# 3_wave_VCO.net
KiCad netlist of a schematic drawn in Altium Designer
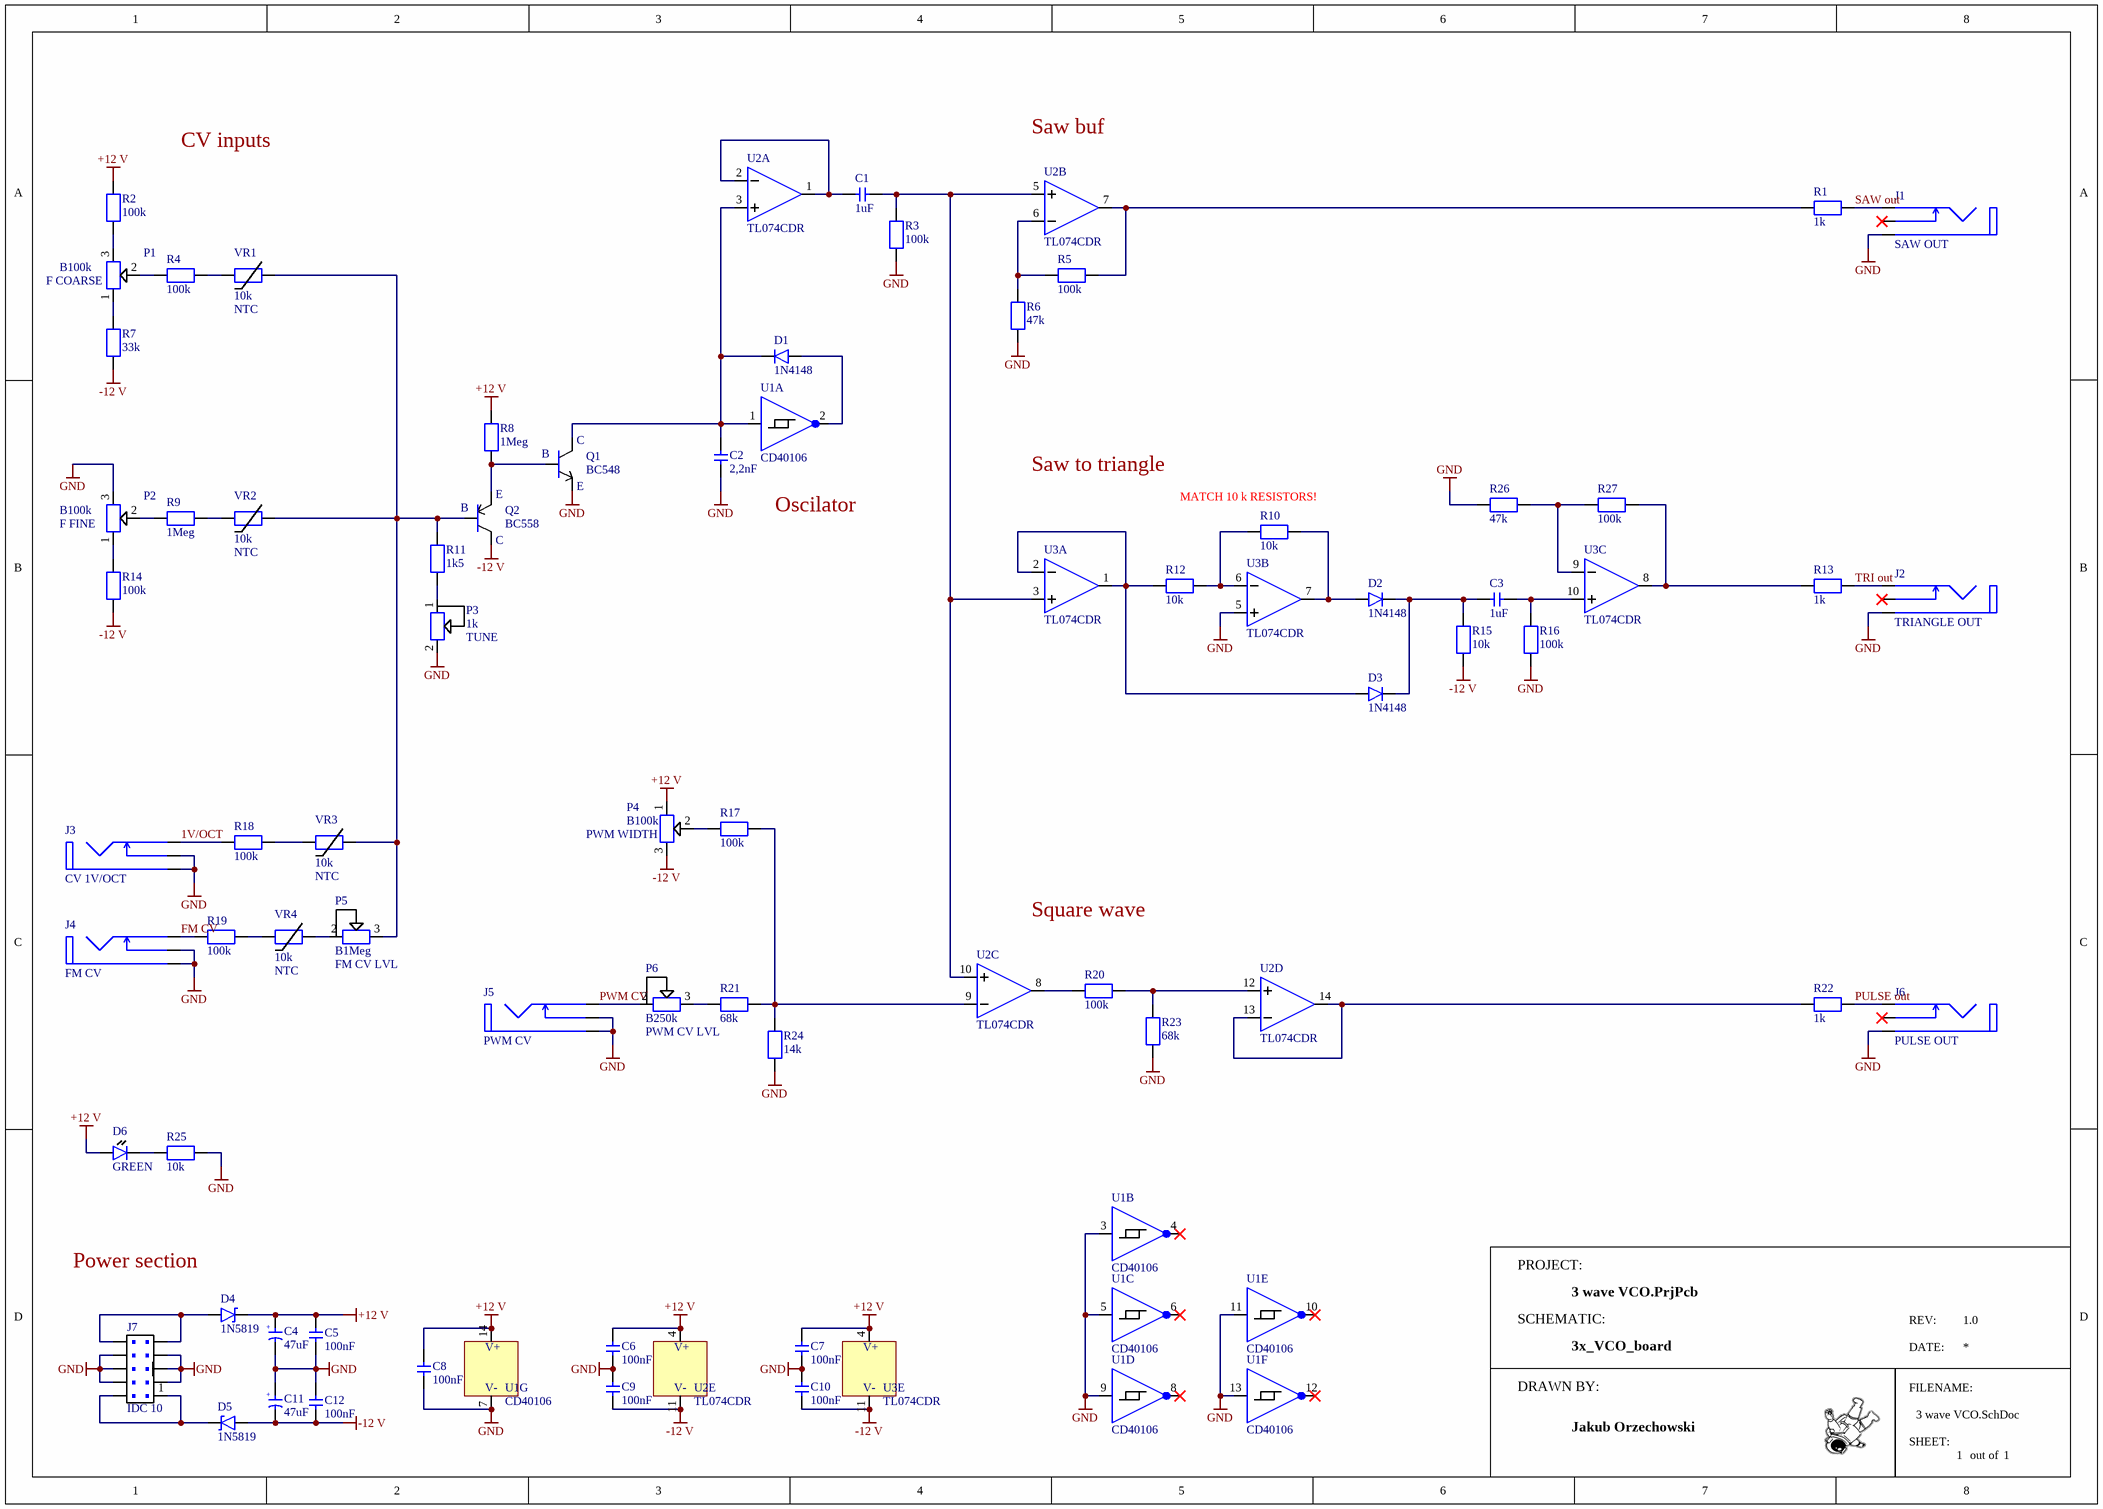
[diagram p0: 3 wave VCO.SchDoc]

(export (version "E")
  (design (tool "Eeschema 10.0.6"))
  (components
    (comp (ref "C1")
      (value "1uF")
      (footprint "Cap THT 5mm")
      (description "THT Capacitor Non-Polarised 5 mm Pitch")
      (fields (field (name "Comment") "CAP"))
      (libsource (lib "Generic components") (part "Capacitor THT 5mm"))
    )
    (comp (ref "C2")
      (value "2,2nF")
      (footprint "Cap THT 5mm")
      (description "THT Capacitor Non-Polarised 5 mm Pitch")
      (fields (field (name "Comment") "CAP"))
      (libsource (lib "Generic components") (part "Capacitor THT 5mm"))
    )
    (comp (ref "C3")
      (value "1uF")
      (footprint "Cap THT 5mm")
      (description "THT Capacitor Non-Polarised 5 mm Pitch")
      (fields (field (name "Comment") "CAP"))
      (libsource (lib "Generic components") (part "Capacitor THT 5mm"))
    )
    (comp (ref "C4")
      (value "47uF")
      (footprint "Cap electrolytic THT 5mm")
      (description "THT Electrolytic Capacitor 5 mm Diameter")
      (fields (field (name "Comment") "CAP"))
      (libsource (lib "Generic components") (part "Capacitor Electr THT 5mm"))
    )
    (comp (ref "C5")
      (value "100nF")
      (footprint "Cap THT 5mm")
      (description "THT Capacitor Non-Polarised 5 mm Pitch")
      (fields (field (name "Comment") "CAP"))
      (libsource (lib "Generic components") (part "Capacitor THT 5mm"))
    )
    (comp (ref "C6")
      (value "100nF")
      (footprint "Cap THT 5mm")
      (description "THT Capacitor Non-Polarised 5 mm Pitch")
      (fields (field (name "Comment") "CAP"))
      (libsource (lib "Generic components") (part "Capacitor THT 5mm"))
    )
    (comp (ref "C7")
      (value "100nF")
      (footprint "Cap THT 5mm")
      (description "THT Capacitor Non-Polarised 5 mm Pitch")
      (fields (field (name "Comment") "CAP"))
      (libsource (lib "Generic components") (part "Capacitor THT 5mm"))
    )
    (comp (ref "C8")
      (value "100nF")
      (footprint "Cap THT 5mm")
      (description "THT Capacitor Non-Polarised 5 mm Pitch")
      (fields (field (name "Comment") "CAP"))
      (libsource (lib "Generic components") (part "Capacitor THT 5mm"))
    )
    (comp (ref "C9")
      (value "100nF")
      (footprint "Cap THT 5mm")
      (description "THT Capacitor Non-Polarised 5 mm Pitch")
      (fields (field (name "Comment") "CAP"))
      (libsource (lib "Generic components") (part "Capacitor THT 5mm"))
    )
    (comp (ref "C10")
      (value "100nF")
      (footprint "Cap THT 5mm")
      (description "THT Capacitor Non-Polarised 5 mm Pitch")
      (fields (field (name "Comment") "CAP"))
      (libsource (lib "Generic components") (part "Capacitor THT 5mm"))
    )
    (comp (ref "C11")
      (value "47uF")
      (footprint "Cap electrolytic THT 5mm")
      (description "THT Electrolytic Capacitor 5 mm Diameter")
      (fields (field (name "Comment") "CAP"))
      (libsource (lib "Generic components") (part "Capacitor Electr THT 5mm"))
    )
    (comp (ref "C12")
      (value "100nF")
      (footprint "Cap THT 5mm")
      (description "THT Capacitor Non-Polarised 5 mm Pitch")
      (fields (field (name "Comment") "CAP"))
      (libsource (lib "Generic components") (part "Capacitor THT 5mm"))
    )
    (comp (ref "D1")
      (value "DIODE")
      (footprint "Diode THT 10 mm")
      (description "Generic THT Axial Diode 10 mm Pitch")
      (fields (field (name "MODEL") "1N4148"))
      (libsource (lib "Diodes") (part "Diode THT"))
    )
    (comp (ref "D2")
      (value "DIODE")
      (footprint "Diode THT 10 mm")
      (description "Generic THT Axial Diode 10 mm Pitch")
      (fields (field (name "MODEL") "1N4148"))
      (libsource (lib "Diodes") (part "Diode THT"))
    )
    (comp (ref "D3")
      (value "DIODE")
      (footprint "Diode THT 10 mm")
      (description "Generic THT Axial Diode 10 mm Pitch")
      (fields (field (name "MODEL") "1N4148"))
      (libsource (lib "Diodes") (part "Diode THT"))
    )
    (comp (ref "D4")
      (value "SCHOTTKY")
      (footprint "Diode THT 10 mm")
      (description "Generic THT Axial Schottky Diode 10 mm Pitch")
      (fields (field (name "MODEL") "1N5819"))
      (libsource (lib "Diodes") (part "Schottky Diode THT"))
    )
    (comp (ref "D5")
      (value "SCHOTTKY")
      (footprint "Diode THT 10 mm")
      (description "Generic THT Axial Schottky Diode 10 mm Pitch")
      (fields (field (name "MODEL") "1N5819"))
      (libsource (lib "Diodes") (part "Schottky Diode THT"))
    )
    (comp (ref "D6")
      (value "LED")
      (footprint "LED SMD 0805")
      (description "SMD LED Diode 0805 Package")
      (fields (field (name "COLOR") "GREEN"))
      (libsource (lib "Opto") (part "LED SMD"))
    )
    (comp (ref "J1")
      (value "JACK Mono")
      (footprint "PJ301M")
      (description "PJ301M Eurorack 3,5 mm Patch Socket PCB Mount")
      (fields (field (name "LABEL") "SAW OUT"))
      (libsource (lib "Connectors") (part "PJ301M"))
    )
    (comp (ref "J2")
      (value "JACK Mono")
      (footprint "PJ301M")
      (description "PJ301M Eurorack 3,5 mm Patch Socket PCB Mount")
      (fields (field (name "LABEL") "TRIANGLE OUT"))
      (libsource (lib "Connectors") (part "PJ301M"))
    )
    (comp (ref "J3")
      (value "JACK Mono")
      (footprint "PJ301M")
      (description "PJ301M Eurorack 3,5 mm Patch Socket PCB Mount")
      (fields (field (name "LABEL") "CV 1V/OCT"))
      (libsource (lib "Connectors") (part "PJ301M"))
    )
    (comp (ref "J4")
      (value "JACK Mono")
      (footprint "PJ301M")
      (description "PJ301M Eurorack 3,5 mm Patch Socket PCB Mount")
      (fields (field (name "LABEL") "FM CV"))
      (libsource (lib "Connectors") (part "PJ301M"))
    )
    (comp (ref "J5")
      (value "JACK Mono")
      (footprint "PJ301M")
      (description "PJ301M Eurorack 3,5 mm Patch Socket PCB Mount")
      (fields (field (name "LABEL") "PWM CV"))
      (libsource (lib "Connectors") (part "PJ301M"))
    )
    (comp (ref "J6")
      (value "JACK Mono")
      (footprint "PJ301M")
      (description "PJ301M Eurorack 3,5 mm Patch Socket PCB Mount")
      (fields (field (name "LABEL") "PULSE OUT"))
      (libsource (lib "Connectors") (part "PJ301M"))
    )
    (comp (ref "J7")
      (value "IDC 10")
      (footprint "IDC 10 PIN")
      (description "10 Pin IDC Connector")
      (libsource (lib "Connectors") (part "IDC 10 pin"))
    )
    (comp (ref "P1")
      (value "B100k")
      (footprint "Alpha 9mm mono")
      (description "PCB Mount Alpha 9mm Mono Potentiometer THT")
      (fields (field (name "PARAMETER") "F COARSE") (field (name "Comment") "Mono Pot"))
      (libsource (lib "Potentiometers") (part "Potentiometer Alpha 9mm mono"))
    )
    (comp (ref "P2")
      (value "B100k")
      (footprint "9 mm PCB Potentiometer")
      (description "PCB Mount 9mm Mono Potentiometer THT")
      (fields (field (name "PARAMETER") "F FINE") (field (name "Comment") "Mono Pot"))
      (libsource (lib "Potentiometers") (part "Potentiometer 9 mm"))
    )
    (comp (ref "P3")
      (value "1k")
      (footprint "Multiturn Potentiometer inline")
      (description "PCB Mount Multiturn Trimmer Potentiometer Top Adjustable as Variable Resistor Clockwise Increase")
      (fields (field (name "PARAMETER") "TUNE") (field (name "Comment") "VR"))
      (libsource (lib "Potentiometers") (part "VR A Multiturn THT"))
    )
    (comp (ref "P4")
      (value "B100k")
      (footprint "9 mm PCB Potentiometer")
      (description "PCB Mount 9mm Mono Potentiometer THT")
      (fields (field (name "PARAMETER") "PWM WIDTH") (field (name "Comment") "Mono Pot"))
      (libsource (lib "Potentiometers") (part "Potentiometer 9 mm"))
    )
    (comp (ref "P5")
      (value "B1Meg")
      (footprint "9 mm PCB Potentiometer")
      (description "PCB Mount 9mm Mono Potentiometer THT as Variable Resistor Clockwise Decrease")
      (fields (field (name "PARAMETER") "FM CV LVL") (field (name "Comment") "VR"))
      (libsource (lib "Potentiometers") (part "VR B 9 mm"))
    )
    (comp (ref "P6")
      (value "B250k")
      (footprint "9 mm PCB Potentiometer")
      (description "PCB Mount 9mm Mono Potentiometer THT as Variable Resistor Clockwise Decrease")
      (fields (field (name "PARAMETER") "PWM CV LVL") (field (name "Comment") "VR"))
      (libsource (lib "Potentiometers") (part "VR B 9 mm"))
    )
    (comp (ref "Q1")
      (value "BC548")
      (footprint "TO-92 wide")
      (description "BC548 NPN Transistor THT TO-92 Package")
      (libsource (lib "Transistors") (part "BC548"))
    )
    (comp (ref "Q2")
      (value "BC558")
      (footprint "TO-92 wide")
      (description "BC558 PNP Transistor THT TO-92 Package")
      (libsource (lib "Transistors") (part "BC558"))
    )
    (comp (ref "R1")
      (value "1k")
      (footprint "Resistor THT vertical")
      (description "THT Axial Resistor 10mm Pitch")
      (fields (field (name "Comment") "RES"))
      (libsource (lib "Generic components") (part "Resistor THT"))
    )
    (comp (ref "R2")
      (value "100k")
      (footprint "Resistor THT vertical")
      (description "THT Axial Resistor 10mm Pitch")
      (fields (field (name "Comment") "RES"))
      (libsource (lib "Generic components") (part "Resistor THT"))
    )
    (comp (ref "R3")
      (value "100k")
      (footprint "Resistor THT vertical")
      (description "THT Axial Resistor 10mm Pitch")
      (fields (field (name "Comment") "RES"))
      (libsource (lib "Generic components") (part "Resistor THT"))
    )
    (comp (ref "R4")
      (value "100k")
      (footprint "Resistor THT vertical")
      (description "THT Axial Resistor 10mm Pitch")
      (fields (field (name "Comment") "RES"))
      (libsource (lib "Generic components") (part "Resistor THT"))
    )
    (comp (ref "R5")
      (value "100k")
      (footprint "Resistor THT vertical")
      (description "THT Axial Resistor 10mm Pitch")
      (fields (field (name "Comment") "RES"))
      (libsource (lib "Generic components") (part "Resistor THT"))
    )
    (comp (ref "R6")
      (value "47k")
      (footprint "Resistor THT vertical")
      (description "THT Axial Resistor 10mm Pitch")
      (fields (field (name "Comment") "RES"))
      (libsource (lib "Generic components") (part "Resistor THT"))
    )
    (comp (ref "R7")
      (value "33k")
      (footprint "Resistor THT vertical")
      (description "THT Axial Resistor 10mm Pitch")
      (fields (field (name "Comment") "RES"))
      (libsource (lib "Generic components") (part "Resistor THT"))
    )
    (comp (ref "R8")
      (value "1Meg")
      (footprint "Resistor THT vertical")
      (description "THT Axial Resistor 10mm Pitch")
      (fields (field (name "Comment") "RES"))
      (libsource (lib "Generic components") (part "Resistor THT"))
    )
    (comp (ref "R9")
      (value "1Meg")
      (footprint "Resistor THT vertical")
      (description "THT Axial Resistor 10mm Pitch")
      (fields (field (name "Comment") "RES"))
      (libsource (lib "Generic components") (part "Resistor THT"))
    )
    (comp (ref "R10")
      (value "10k")
      (footprint "Resistor THT vertical")
      (description "THT Axial Resistor 10mm Pitch")
      (fields (field (name "Comment") "RES"))
      (libsource (lib "Generic components") (part "Resistor THT"))
    )
    (comp (ref "R11")
      (value "1k5")
      (footprint "Resistor THT vertical")
      (description "THT Axial Resistor 10mm Pitch")
      (fields (field (name "Comment") "RES"))
      (libsource (lib "Generic components") (part "Resistor THT"))
    )
    (comp (ref "R12")
      (value "10k")
      (footprint "Resistor THT vertical")
      (description "THT Axial Resistor 10mm Pitch")
      (fields (field (name "Comment") "RES"))
      (libsource (lib "Generic components") (part "Resistor THT"))
    )
    (comp (ref "R13")
      (value "1k")
      (footprint "Resistor THT vertical")
      (description "THT Axial Resistor 10mm Pitch")
      (fields (field (name "Comment") "RES"))
      (libsource (lib "Generic components") (part "Resistor THT"))
    )
    (comp (ref "R14")
      (value "100k")
      (footprint "Resistor THT vertical")
      (description "THT Axial Resistor 10mm Pitch")
      (fields (field (name "Comment") "RES"))
      (libsource (lib "Generic components") (part "Resistor THT"))
    )
    (comp (ref "R15")
      (value "10k")
      (footprint "Resistor THT vertical")
      (description "THT Axial Resistor 10mm Pitch")
      (fields (field (name "Comment") "RES"))
      (libsource (lib "Generic components") (part "Resistor THT"))
    )
    (comp (ref "R16")
      (value "100k")
      (footprint "Resistor THT vertical")
      (description "THT Axial Resistor 10mm Pitch")
      (fields (field (name "Comment") "RES"))
      (libsource (lib "Generic components") (part "Resistor THT"))
    )
    (comp (ref "R17")
      (value "100k")
      (footprint "Resistor THT vertical")
      (description "THT Axial Resistor 10mm Pitch")
      (fields (field (name "Comment") "RES"))
      (libsource (lib "Generic components") (part "Resistor THT"))
    )
    (comp (ref "R18")
      (value "100k")
      (footprint "Resistor THT vertical")
      (description "THT Axial Resistor 10mm Pitch")
      (fields (field (name "Comment") "RES"))
      (libsource (lib "Generic components") (part "Resistor THT"))
    )
    (comp (ref "R19")
      (value "100k")
      (footprint "Resistor THT vertical")
      (description "THT Axial Resistor 10mm Pitch")
      (fields (field (name "Comment") "RES"))
      (libsource (lib "Generic components") (part "Resistor THT"))
    )
    (comp (ref "R20")
      (value "100k")
      (footprint "Resistor THT vertical")
      (description "THT Axial Resistor 10mm Pitch")
      (fields (field (name "Comment") "RES"))
      (libsource (lib "Generic components") (part "Resistor THT"))
    )
    (comp (ref "R21")
      (value "68k")
      (footprint "Resistor THT vertical")
      (description "THT Axial Resistor 10mm Pitch")
      (fields (field (name "Comment") "RES"))
      (libsource (lib "Generic components") (part "Resistor THT"))
    )
    (comp (ref "R22")
      (value "1k")
      (footprint "Resistor THT vertical")
      (description "THT Axial Resistor 10mm Pitch")
      (fields (field (name "Comment") "RES"))
      (libsource (lib "Generic components") (part "Resistor THT"))
    )
    (comp (ref "R23")
      (value "68k")
      (footprint "Resistor THT vertical")
      (description "THT Axial Resistor 10mm Pitch")
      (fields (field (name "Comment") "RES"))
      (libsource (lib "Generic components") (part "Resistor THT"))
    )
    (comp (ref "R24")
      (value "14k")
      (footprint "Resistor THT vertical")
      (description "THT Axial Resistor 10mm Pitch")
      (fields (field (name "Comment") "RES"))
      (libsource (lib "Generic components") (part "Resistor THT"))
    )
    (comp (ref "R25")
      (value "10k")
      (footprint "Resistor SMD 0805")
      (description "SMD Resistor 0805 package")
      (fields (field (name "Comment") "RES"))
      (libsource (lib "Generic components") (part "Resistor SMD 0805"))
    )
    (comp (ref "R26")
      (value "47k")
      (footprint "Resistor THT vertical")
      (description "THT Axial Resistor 10mm Pitch")
      (fields (field (name "Comment") "RES"))
      (libsource (lib "Generic components") (part "Resistor THT"))
    )
    (comp (ref "R27")
      (value "100k")
      (footprint "Resistor THT vertical")
      (description "THT Axial Resistor 10mm Pitch")
      (fields (field (name "Comment") "RES"))
      (libsource (lib "Generic components") (part "Resistor THT"))
    )
    (comp (ref "U1")
      (value "CD40106")
      (footprint "DIP-14 socket")
      (description "CD40106 Hex Schmitt Trigger Inverter DIP-14 Package")
      (libsource (lib "ICs") (part "CD40106 DIP-14"))
    )
    (comp (ref "U2")
      (value "TL074CDR")
      (footprint "SOIC14")
      (description "TL074CDR Quad Op-Amp SOIC14 Package")
      (libsource (lib "OpAmps") (part "TL074CDR SOIC14"))
    )
    (comp (ref "U3")
      (value "TL074CDR")
      (footprint "SOIC14")
      (description "TL074CDR Quad Op-Amp SOIC14 Package")
      (libsource (lib "") (part "TL074CDR SOIC14_1"))
    )
    (comp (ref "VR1")
      (value "NTC")
      (footprint "THERMISTOR THT 2,54 MM")
      (description "THT NTC Thermistor 2,54 mm Pitch")
      (fields (field (name "ALTIUM_VALUE") "10k"))
      (libsource (lib "Generic components") (part "Thermistor NTC THT"))
    )
    (comp (ref "VR2")
      (value "NTC")
      (footprint "THERMISTOR THT 2,54 MM")
      (description "THT NTC Thermistor 2,54 mm Pitch")
      (fields (field (name "ALTIUM_VALUE") "10k"))
      (libsource (lib "Generic components") (part "Thermistor NTC THT"))
    )
    (comp (ref "VR3")
      (value "NTC")
      (footprint "THERMISTOR THT 2,54 MM")
      (description "THT NTC Thermistor 2,54 mm Pitch")
      (fields (field (name "ALTIUM_VALUE") "10k"))
      (libsource (lib "Generic components") (part "Thermistor NTC THT"))
    )
    (comp (ref "VR4")
      (value "NTC")
      (footprint "THERMISTOR THT 2,54 MM")
      (description "THT NTC Thermistor 2,54 mm Pitch")
      (fields (field (name "ALTIUM_VALUE") "10k"))
      (libsource (lib "Generic components") (part "Thermistor NTC THT"))
    )
  )
  (nets
    (net (code "1") (name "+12 V") (class "Default")
      (node (ref "C4") (pin "2") (pintype "passive"))
      (node (ref "C5") (pin "2") (pintype "passive"))
      (node (ref "C6") (pin "2") (pintype "passive"))
      (node (ref "C7") (pin "2") (pintype "passive"))
      (node (ref "C8") (pin "2") (pintype "passive"))
      (node (ref "D4") (pin "2") (pintype "passive"))
      (node (ref "D6") (pin "1") (pintype "passive"))
      (node (ref "P4") (pin "1") (pintype "passive"))
      (node (ref "R2") (pin "2") (pintype "passive"))
      (node (ref "R8") (pin "1") (pintype "passive"))
      (node (ref "U1") (pin "14") (pintype "passive"))
      (node (ref "U2") (pin "4") (pintype "passive"))
      (node (ref "U3") (pin "4") (pintype "passive"))
    )
    (net (code "2") (name "-12 V") (class "Default")
      (node (ref "C10") (pin "1") (pintype "passive"))
      (node (ref "C11") (pin "1") (pintype "passive"))
      (node (ref "C12") (pin "1") (pintype "passive"))
      (node (ref "C9") (pin "1") (pintype "passive"))
      (node (ref "D5") (pin "1") (pintype "passive"))
      (node (ref "P4") (pin "3") (pintype "passive"))
      (node (ref "Q2") (pin "1") (pintype "passive"))
      (node (ref "R14") (pin "1") (pintype "passive"))
      (node (ref "R15") (pin "2") (pintype "passive"))
      (node (ref "R7") (pin "1") (pintype "passive"))
      (node (ref "U2") (pin "11") (pintype "passive"))
      (node (ref "U3") (pin "11") (pintype "passive"))
    )
    (net (code "3") (name "/1V{slash}OCT") (class "Default")
      (node (ref "J3") (pin "3") (pintype "passive"))
      (node (ref "R18") (pin "2") (pintype "passive"))
    )
    (net (code "4") (name "/FM CV") (class "Default")
      (node (ref "J4") (pin "3") (pintype "passive"))
      (node (ref "R19") (pin "2") (pintype "passive"))
    )
    (net (code "5") (name "/PULSE out") (class "Default")
      (node (ref "J6") (pin "3") (pintype "passive"))
      (node (ref "R22") (pin "2") (pintype "passive"))
    )
    (net (code "6") (name "/PWM CV") (class "Default")
      (node (ref "J5") (pin "3") (pintype "passive"))
      (node (ref "P6") (pin "2") (pintype "passive"))
    )
    (net (code "7") (name "/SAW out") (class "Default")
      (node (ref "J1") (pin "3") (pintype "passive"))
      (node (ref "R1") (pin "2") (pintype "passive"))
    )
    (net (code "8") (name "/TRI out") (class "Default")
      (node (ref "J2") (pin "3") (pintype "passive"))
      (node (ref "R13") (pin "2") (pintype "passive"))
    )
    (net (code "9") (name "GND") (class "Default")
      (node (ref "C10") (pin "2") (pintype "passive"))
      (node (ref "C11") (pin "2") (pintype "passive"))
      (node (ref "C12") (pin "2") (pintype "passive"))
      (node (ref "C2") (pin "1") (pintype "passive"))
      (node (ref "C4") (pin "1") (pintype "passive"))
      (node (ref "C5") (pin "1") (pintype "passive"))
      (node (ref "C6") (pin "1") (pintype "passive"))
      (node (ref "C7") (pin "1") (pintype "passive"))
      (node (ref "C8") (pin "1") (pintype "passive"))
      (node (ref "C9") (pin "2") (pintype "passive"))
      (node (ref "J1") (pin "1") (pintype "passive"))
      (node (ref "J2") (pin "1") (pintype "passive"))
      (node (ref "J3") (pin "1") (pintype "passive"))
      (node (ref "J3") (pin "2") (pintype "passive"))
      (node (ref "J4") (pin "1") (pintype "passive"))
      (node (ref "J4") (pin "2") (pintype "passive"))
      (node (ref "J5") (pin "1") (pintype "passive"))
      (node (ref "J5") (pin "2") (pintype "passive"))
      (node (ref "J6") (pin "1") (pintype "passive"))
      (node (ref "J7") (pin "3") (pintype "passive"))
      (node (ref "J7") (pin "4") (pintype "passive"))
      (node (ref "J7") (pin "5") (pintype "passive"))
      (node (ref "J7") (pin "6") (pintype "passive"))
      (node (ref "J7") (pin "7") (pintype "passive"))
      (node (ref "J7") (pin "8") (pintype "passive"))
      (node (ref "P2") (pin "3") (pintype "passive"))
      (node (ref "P3") (pin "2") (pintype "passive"))
      (node (ref "Q1") (pin "3") (pintype "passive"))
      (node (ref "R16") (pin "2") (pintype "passive"))
      (node (ref "R23") (pin "1") (pintype "passive"))
      (node (ref "R24") (pin "1") (pintype "passive"))
      (node (ref "R25") (pin "2") (pintype "passive"))
      (node (ref "R26") (pin "1") (pintype "passive"))
      (node (ref "R3") (pin "2") (pintype "passive"))
      (node (ref "R6") (pin "2") (pintype "passive"))
      (node (ref "U1") (pin "11") (pintype "passive"))
      (node (ref "U1") (pin "13") (pintype "passive"))
      (node (ref "U1") (pin "3") (pintype "passive"))
      (node (ref "U1") (pin "5") (pintype "passive"))
      (node (ref "U1") (pin "7") (pintype "passive"))
      (node (ref "U1") (pin "9") (pintype "passive"))
      (node (ref "U3") (pin "5") (pintype "passive"))
    )
    (net (code "10") (name "Net-(C1-Pad1)") (class "Default")
      (node (ref "C1") (pin "1") (pintype "passive"))
      (node (ref "R3") (pin "1") (pintype "passive"))
      (node (ref "U2") (pin "10") (pintype "passive"))
      (node (ref "U2") (pin "5") (pintype "passive"))
      (node (ref "U3") (pin "3") (pintype "passive"))
    )
    (net (code "11") (name "Net-(C1-Pad2)") (class "Default")
      (node (ref "C1") (pin "2") (pintype "passive"))
      (node (ref "U2") (pin "1") (pintype "passive"))
      (node (ref "U2") (pin "2") (pintype "passive"))
    )
    (net (code "12") (name "Net-(C2-Pad2)") (class "Default")
      (node (ref "C2") (pin "2") (pintype "passive"))
      (node (ref "D1") (pin "2") (pintype "passive"))
      (node (ref "Q1") (pin "1") (pintype "passive"))
      (node (ref "U1") (pin "1") (pintype "passive"))
      (node (ref "U2") (pin "3") (pintype "passive"))
    )
    (net (code "13") (name "Net-(C3-Pad1)") (class "Default")
      (node (ref "C3") (pin "1") (pintype "passive"))
      (node (ref "R16") (pin "1") (pintype "passive"))
      (node (ref "U3") (pin "10") (pintype "passive"))
    )
    (net (code "14") (name "Net-(C3-Pad2)") (class "Default")
      (node (ref "C3") (pin "2") (pintype "passive"))
      (node (ref "D2") (pin "2") (pintype "passive"))
      (node (ref "D3") (pin "2") (pintype "passive"))
      (node (ref "R15") (pin "1") (pintype "passive"))
    )
    (net (code "15") (name "Net-(D1-Pad1)") (class "Default")
      (node (ref "D1") (pin "1") (pintype "passive"))
      (node (ref "U1") (pin "2") (pintype "passive"))
    )
    (net (code "16") (name "Net-(D2-Pad1)") (class "Default")
      (node (ref "D2") (pin "1") (pintype "passive"))
      (node (ref "R10") (pin "2") (pintype "passive"))
      (node (ref "U3") (pin "7") (pintype "passive"))
    )
    (net (code "17") (name "Net-(D3-Pad1)") (class "Default")
      (node (ref "D3") (pin "1") (pintype "passive"))
      (node (ref "R12") (pin "1") (pintype "passive"))
      (node (ref "U3") (pin "1") (pintype "passive"))
      (node (ref "U3") (pin "2") (pintype "passive"))
    )
    (net (code "18") (name "Net-(D4-Pad1)") (class "Default")
      (node (ref "D4") (pin "1") (pintype "passive"))
      (node (ref "J7") (pin "10") (pintype "passive"))
      (node (ref "J7") (pin "9") (pintype "passive"))
    )
    (net (code "19") (name "Net-(D5-Pad2)") (class "Default")
      (node (ref "D5") (pin "2") (pintype "passive"))
      (node (ref "J7") (pin "1") (pintype "passive"))
      (node (ref "J7") (pin "2") (pintype "passive"))
    )
    (net (code "20") (name "Net-(D6-Pad2)") (class "Default")
      (node (ref "D6") (pin "2") (pintype "passive"))
      (node (ref "R25") (pin "1") (pintype "passive"))
    )
    (net (code "21") (name "Net-(P1-Pad1)") (class "Default")
      (node (ref "P1") (pin "1") (pintype "passive"))
      (node (ref "R7") (pin "2") (pintype "passive"))
    )
    (net (code "22") (name "Net-(P1-Pad2)") (class "Default")
      (node (ref "P1") (pin "2") (pintype "passive"))
      (node (ref "R4") (pin "2") (pintype "passive"))
    )
    (net (code "23") (name "Net-(P1-Pad3)") (class "Default")
      (node (ref "P1") (pin "3") (pintype "passive"))
      (node (ref "R2") (pin "1") (pintype "passive"))
    )
    (net (code "24") (name "Net-(P2-Pad1)") (class "Default")
      (node (ref "P2") (pin "1") (pintype "passive"))
      (node (ref "R14") (pin "2") (pintype "passive"))
    )
    (net (code "25") (name "Net-(P2-Pad2)") (class "Default")
      (node (ref "P2") (pin "2") (pintype "passive"))
      (node (ref "R9") (pin "2") (pintype "passive"))
    )
    (net (code "26") (name "Net-(P3-Pad1)") (class "Default")
      (node (ref "P3") (pin "1") (pintype "passive"))
      (node (ref "R11") (pin "2") (pintype "passive"))
    )
    (net (code "27") (name "Net-(P4-Pad2)") (class "Default")
      (node (ref "P4") (pin "2") (pintype "passive"))
      (node (ref "R17") (pin "1") (pintype "passive"))
    )
    (net (code "28") (name "Net-(P5-Pad2)") (class "Default")
      (node (ref "P5") (pin "2") (pintype "passive"))
      (node (ref "VR4") (pin "2") (pintype "passive"))
    )
    (net (code "29") (name "Net-(P5-Pad3)") (class "Default")
      (node (ref "P5") (pin "3") (pintype "passive"))
      (node (ref "Q2") (pin "2") (pintype "passive"))
      (node (ref "R11") (pin "1") (pintype "passive"))
      (node (ref "VR1") (pin "2") (pintype "passive"))
      (node (ref "VR2") (pin "2") (pintype "passive"))
      (node (ref "VR3") (pin "2") (pintype "passive"))
    )
    (net (code "30") (name "Net-(P6-Pad3)") (class "Default")
      (node (ref "P6") (pin "3") (pintype "passive"))
      (node (ref "R21") (pin "1") (pintype "passive"))
    )
    (net (code "31") (name "Net-(Q1-Pad2)") (class "Default")
      (node (ref "Q1") (pin "2") (pintype "passive"))
      (node (ref "Q2") (pin "3") (pintype "passive"))
      (node (ref "R8") (pin "2") (pintype "passive"))
    )
    (net (code "32") (name "Net-(R1-Pad1)") (class "Default")
      (node (ref "R1") (pin "1") (pintype "passive"))
      (node (ref "R5") (pin "2") (pintype "passive"))
      (node (ref "U2") (pin "7") (pintype "passive"))
    )
    (net (code "33") (name "Net-(R4-Pad1)") (class "Default")
      (node (ref "R4") (pin "1") (pintype "passive"))
      (node (ref "VR1") (pin "1") (pintype "passive"))
    )
    (net (code "34") (name "Net-(R5-Pad1)") (class "Default")
      (node (ref "R5") (pin "1") (pintype "passive"))
      (node (ref "R6") (pin "1") (pintype "passive"))
      (node (ref "U2") (pin "6") (pintype "passive"))
    )
    (net (code "35") (name "Net-(R9-Pad1)") (class "Default")
      (node (ref "R9") (pin "1") (pintype "passive"))
      (node (ref "VR2") (pin "1") (pintype "passive"))
    )
    (net (code "36") (name "Net-(R10-Pad1)") (class "Default")
      (node (ref "R10") (pin "1") (pintype "passive"))
      (node (ref "R12") (pin "2") (pintype "passive"))
      (node (ref "U3") (pin "6") (pintype "passive"))
    )
    (net (code "37") (name "Net-(R13-Pad1)") (class "Default")
      (node (ref "R13") (pin "1") (pintype "passive"))
      (node (ref "R27") (pin "2") (pintype "passive"))
      (node (ref "U3") (pin "8") (pintype "passive"))
    )
    (net (code "38") (name "Net-(R17-Pad2)") (class "Default")
      (node (ref "R17") (pin "2") (pintype "passive"))
      (node (ref "R21") (pin "2") (pintype "passive"))
      (node (ref "R24") (pin "2") (pintype "passive"))
      (node (ref "U2") (pin "9") (pintype "passive"))
    )
    (net (code "39") (name "Net-(R18-Pad1)") (class "Default")
      (node (ref "R18") (pin "1") (pintype "passive"))
      (node (ref "VR3") (pin "1") (pintype "passive"))
    )
    (net (code "40") (name "Net-(R19-Pad1)") (class "Default")
      (node (ref "R19") (pin "1") (pintype "passive"))
      (node (ref "VR4") (pin "1") (pintype "passive"))
    )
    (net (code "41") (name "Net-(R20-Pad1)") (class "Default")
      (node (ref "R20") (pin "1") (pintype "passive"))
      (node (ref "U2") (pin "8") (pintype "passive"))
    )
    (net (code "42") (name "Net-(R20-Pad2)") (class "Default")
      (node (ref "R20") (pin "2") (pintype "passive"))
      (node (ref "R23") (pin "2") (pintype "passive"))
      (node (ref "U2") (pin "12") (pintype "passive"))
    )
    (net (code "43") (name "Net-(R22-Pad1)") (class "Default")
      (node (ref "R22") (pin "1") (pintype "passive"))
      (node (ref "U2") (pin "13") (pintype "passive"))
      (node (ref "U2") (pin "14") (pintype "passive"))
    )
    (net (code "44") (name "Net-(R26-Pad2)") (class "Default")
      (node (ref "R26") (pin "2") (pintype "passive"))
      (node (ref "R27") (pin "1") (pintype "passive"))
      (node (ref "U3") (pin "9") (pintype "passive"))
    )
    (net (code "45") (name "unconnected-(J1-Pad2)") (class "Default")
      (node (ref "J1") (pin "2") (pintype "passive+no_connect"))
    )
    (net (code "46") (name "unconnected-(J2-Pad2)") (class "Default")
      (node (ref "J2") (pin "2") (pintype "passive+no_connect"))
    )
    (net (code "47") (name "unconnected-(J6-Pad2)") (class "Default")
      (node (ref "J6") (pin "2") (pintype "passive+no_connect"))
    )
    (net (code "48") (name "unconnected-(U1-Pad4)") (class "Default")
      (node (ref "U1") (pin "4") (pintype "passive+no_connect"))
    )
    (net (code "49") (name "unconnected-(U1-Pad6)") (class "Default")
      (node (ref "U1") (pin "6") (pintype "passive+no_connect"))
    )
    (net (code "50") (name "unconnected-(U1-Pad8)") (class "Default")
      (node (ref "U1") (pin "8") (pintype "passive+no_connect"))
    )
    (net (code "51") (name "unconnected-(U1-Pad10)") (class "Default")
      (node (ref "U1") (pin "10") (pintype "passive+no_connect"))
    )
    (net (code "52") (name "unconnected-(U1-Pad12)") (class "Default")
      (node (ref "U1") (pin "12") (pintype "passive+no_connect"))
    )
  )
)
